# CAS_Interface.net
KiCad netlist of a schematic drawn in Altium Designer
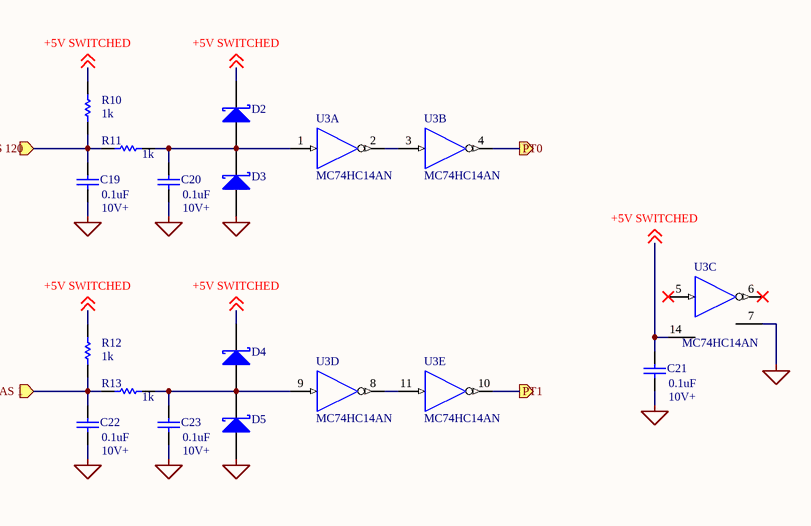
[diagram p0: CAS Interface.SchDoc]

(export (version "E")
  (design (tool "Eeschema 10.0.6"))
  (components
    (comp (ref "C19")
      (value "0.1uF")
      (footprint "RAD-0.3")
      (description "Capacitor")
      (fields (field (name "PUBLISHER") "Altium Limited"))
      (libsource (lib "Miscellaneous Devices") (part "Cap"))
    )
    (comp (ref "C20")
      (value "0.1uF")
      (footprint "RAD-0.3")
      (description "Capacitor")
      (fields (field (name "PUBLISHER") "Altium Limited"))
      (libsource (lib "Miscellaneous Devices") (part "Cap"))
    )
    (comp (ref "C21")
      (value "0.1uF")
      (footprint "RAD-0.3")
      (description "Capacitor")
      (fields (field (name "PUBLISHER") "Altium Limited"))
      (libsource (lib "Miscellaneous Devices") (part "Cap"))
    )
    (comp (ref "C22")
      (value "0.1uF")
      (footprint "RAD-0.3")
      (description "Capacitor")
      (fields (field (name "PUBLISHER") "Altium Limited"))
      (libsource (lib "Miscellaneous Devices") (part "Cap"))
    )
    (comp (ref "C23")
      (value "0.1uF")
      (footprint "RAD-0.3")
      (description "Capacitor")
      (fields (field (name "PUBLISHER") "Altium Limited"))
      (libsource (lib "Miscellaneous Devices") (part "Cap"))
    )
    (comp (ref "D2")
      (value "~")
      (footprint "SMB")
      (description "Schottky Diode")
      (fields (field (name "PUBLISHER") "Altium Limited"))
      (libsource (lib "Miscellaneous Devices") (part "D Schottky"))
    )
    (comp (ref "D3")
      (value "~")
      (footprint "SMB")
      (description "Schottky Diode")
      (fields (field (name "PUBLISHER") "Altium Limited"))
      (libsource (lib "Miscellaneous Devices") (part "D Schottky"))
    )
    (comp (ref "D4")
      (value "~")
      (footprint "SMB")
      (description "Schottky Diode")
      (fields (field (name "PUBLISHER") "Altium Limited"))
      (libsource (lib "Miscellaneous Devices") (part "D Schottky"))
    )
    (comp (ref "D5")
      (value "~")
      (footprint "SMB")
      (description "Schottky Diode")
      (fields (field (name "PUBLISHER") "Altium Limited"))
      (libsource (lib "Miscellaneous Devices") (part "D Schottky"))
    )
    (comp (ref "R10")
      (value "1k")
      (footprint "AXIAL-0.3")
      (description "Resistor")
      (fields (field (name "PUBLISHER") "Altium Limited"))
      (libsource (lib "Miscellaneous Devices") (part "Res1"))
    )
    (comp (ref "R11")
      (value "1k")
      (footprint "AXIAL-0.3")
      (description "Resistor")
      (fields (field (name "PUBLISHER") "Altium Limited"))
      (libsource (lib "Miscellaneous Devices") (part "Res1"))
    )
    (comp (ref "R12")
      (value "1k")
      (footprint "AXIAL-0.3")
      (description "Resistor")
      (fields (field (name "PUBLISHER") "Altium Limited"))
      (libsource (lib "Miscellaneous Devices") (part "Res1"))
    )
    (comp (ref "R13")
      (value "1k")
      (footprint "AXIAL-0.3")
      (description "Resistor")
      (fields (field (name "PUBLISHER") "Altium Limited"))
      (libsource (lib "Miscellaneous Devices") (part "Res1"))
    )
    (comp (ref "U3")
      (value "MC74HC14AN")
      (footprint "646-06")
      (description "Hex Schmitt Trigger Inverter")
      (fields (field (name "PUBLISHER") "Altium Limited"))
      (libsource (lib "Motorola Logic Gate") (part "MC74HC14AN"))
    )
  )
  (nets
    (net (code "1") (name "+5V SWITCHED") (class "Default")
      (node (ref "C21") (pin "2") (pinfunction "2_2") (pintype "passive"))
      (node (ref "D2") (pin "2") (pinfunction "K_2") (pintype "passive"))
      (node (ref "D4") (pin "2") (pinfunction "K_2") (pintype "passive"))
      (node (ref "R10") (pin "1") (pinfunction "1_1") (pintype "passive"))
      (node (ref "R12") (pin "1") (pinfunction "1_1") (pintype "passive"))
      (node (ref "U3") (pin "14") (pinfunction "VDD_14") (pintype "power_in"))
    )
    (net (code "2") (name "/CAS 1") (class "Default")
      (node (ref "C22") (pin "2") (pinfunction "2_2") (pintype "passive"))
      (node (ref "R12") (pin "2") (pinfunction "2_2") (pintype "passive"))
      (node (ref "R13") (pin "1") (pinfunction "1_1") (pintype "passive"))
    )
    (net (code "3") (name "/CAS 120") (class "Default")
      (node (ref "C19") (pin "2") (pinfunction "2_2") (pintype "passive"))
      (node (ref "R10") (pin "2") (pinfunction "2_2") (pintype "passive"))
      (node (ref "R11") (pin "1") (pinfunction "1_1") (pintype "passive"))
    )
    (net (code "4") (name "/PT0") (class "Default")
      (node (ref "U3") (pin "4") (pinfunction "Y_4") (pintype "output"))
    )
    (net (code "5") (name "/PT1") (class "Default")
      (node (ref "U3") (pin "10") (pinfunction "Y_10") (pintype "output"))
    )
    (net (code "6") (name "<NO NET>") (class "Default")
      (node (ref "C19") (pin "1") (pinfunction "1_1") (pintype "passive"))
      (node (ref "C20") (pin "1") (pinfunction "1_1") (pintype "passive"))
      (node (ref "C21") (pin "1") (pinfunction "1_1") (pintype "passive"))
      (node (ref "C22") (pin "1") (pinfunction "1_1") (pintype "passive"))
      (node (ref "C23") (pin "1") (pinfunction "1_1") (pintype "passive"))
      (node (ref "D3") (pin "1") (pinfunction "A_1") (pintype "passive"))
      (node (ref "D5") (pin "1") (pinfunction "A_1") (pintype "passive"))
      (node (ref "U3") (pin "7") (pinfunction "GND_7") (pintype "power_in"))
    )
    (net (code "7") (name "Net-(D2-A)") (class "Default")
      (node (ref "C20") (pin "2") (pinfunction "2_2") (pintype "passive"))
      (node (ref "D2") (pin "1") (pinfunction "A_1") (pintype "passive"))
      (node (ref "D3") (pin "2") (pinfunction "K_2") (pintype "passive"))
      (node (ref "R11") (pin "2") (pinfunction "2_2") (pintype "passive"))
      (node (ref "U3") (pin "1") (pinfunction "A_1") (pintype "input"))
    )
    (net (code "8") (name "Net-(D4-A)") (class "Default")
      (node (ref "C23") (pin "2") (pinfunction "2_2") (pintype "passive"))
      (node (ref "D4") (pin "1") (pinfunction "A_1") (pintype "passive"))
      (node (ref "D5") (pin "2") (pinfunction "K_2") (pintype "passive"))
      (node (ref "R13") (pin "2") (pinfunction "2_2") (pintype "passive"))
      (node (ref "U3") (pin "9") (pinfunction "A_9") (pintype "input"))
    )
    (net (code "9") (name "Net-(U3A-Y)") (class "Default")
      (node (ref "U3") (pin "2") (pinfunction "Y_2") (pintype "output"))
      (node (ref "U3") (pin "3") (pinfunction "A_3") (pintype "input"))
    )
    (net (code "10") (name "Net-(U3D-Y)") (class "Default")
      (node (ref "U3") (pin "11") (pinfunction "A_11") (pintype "input"))
      (node (ref "U3") (pin "8") (pinfunction "Y_8") (pintype "output"))
    )
    (net (code "11") (name "unconnected-(U3C-A-Pad5)") (class "Default")
      (node (ref "U3") (pin "5") (pinfunction "A_5") (pintype "input+no_connect"))
    )
    (net (code "12") (name "unconnected-(U3C-Y-Pad6)") (class "Default")
      (node (ref "U3") (pin "6") (pinfunction "Y_6") (pintype "output+no_connect"))
    )
  )
)
